# 01_USB_B_and_Power.net
KiCad netlist of a schematic drawn in Altium Designer
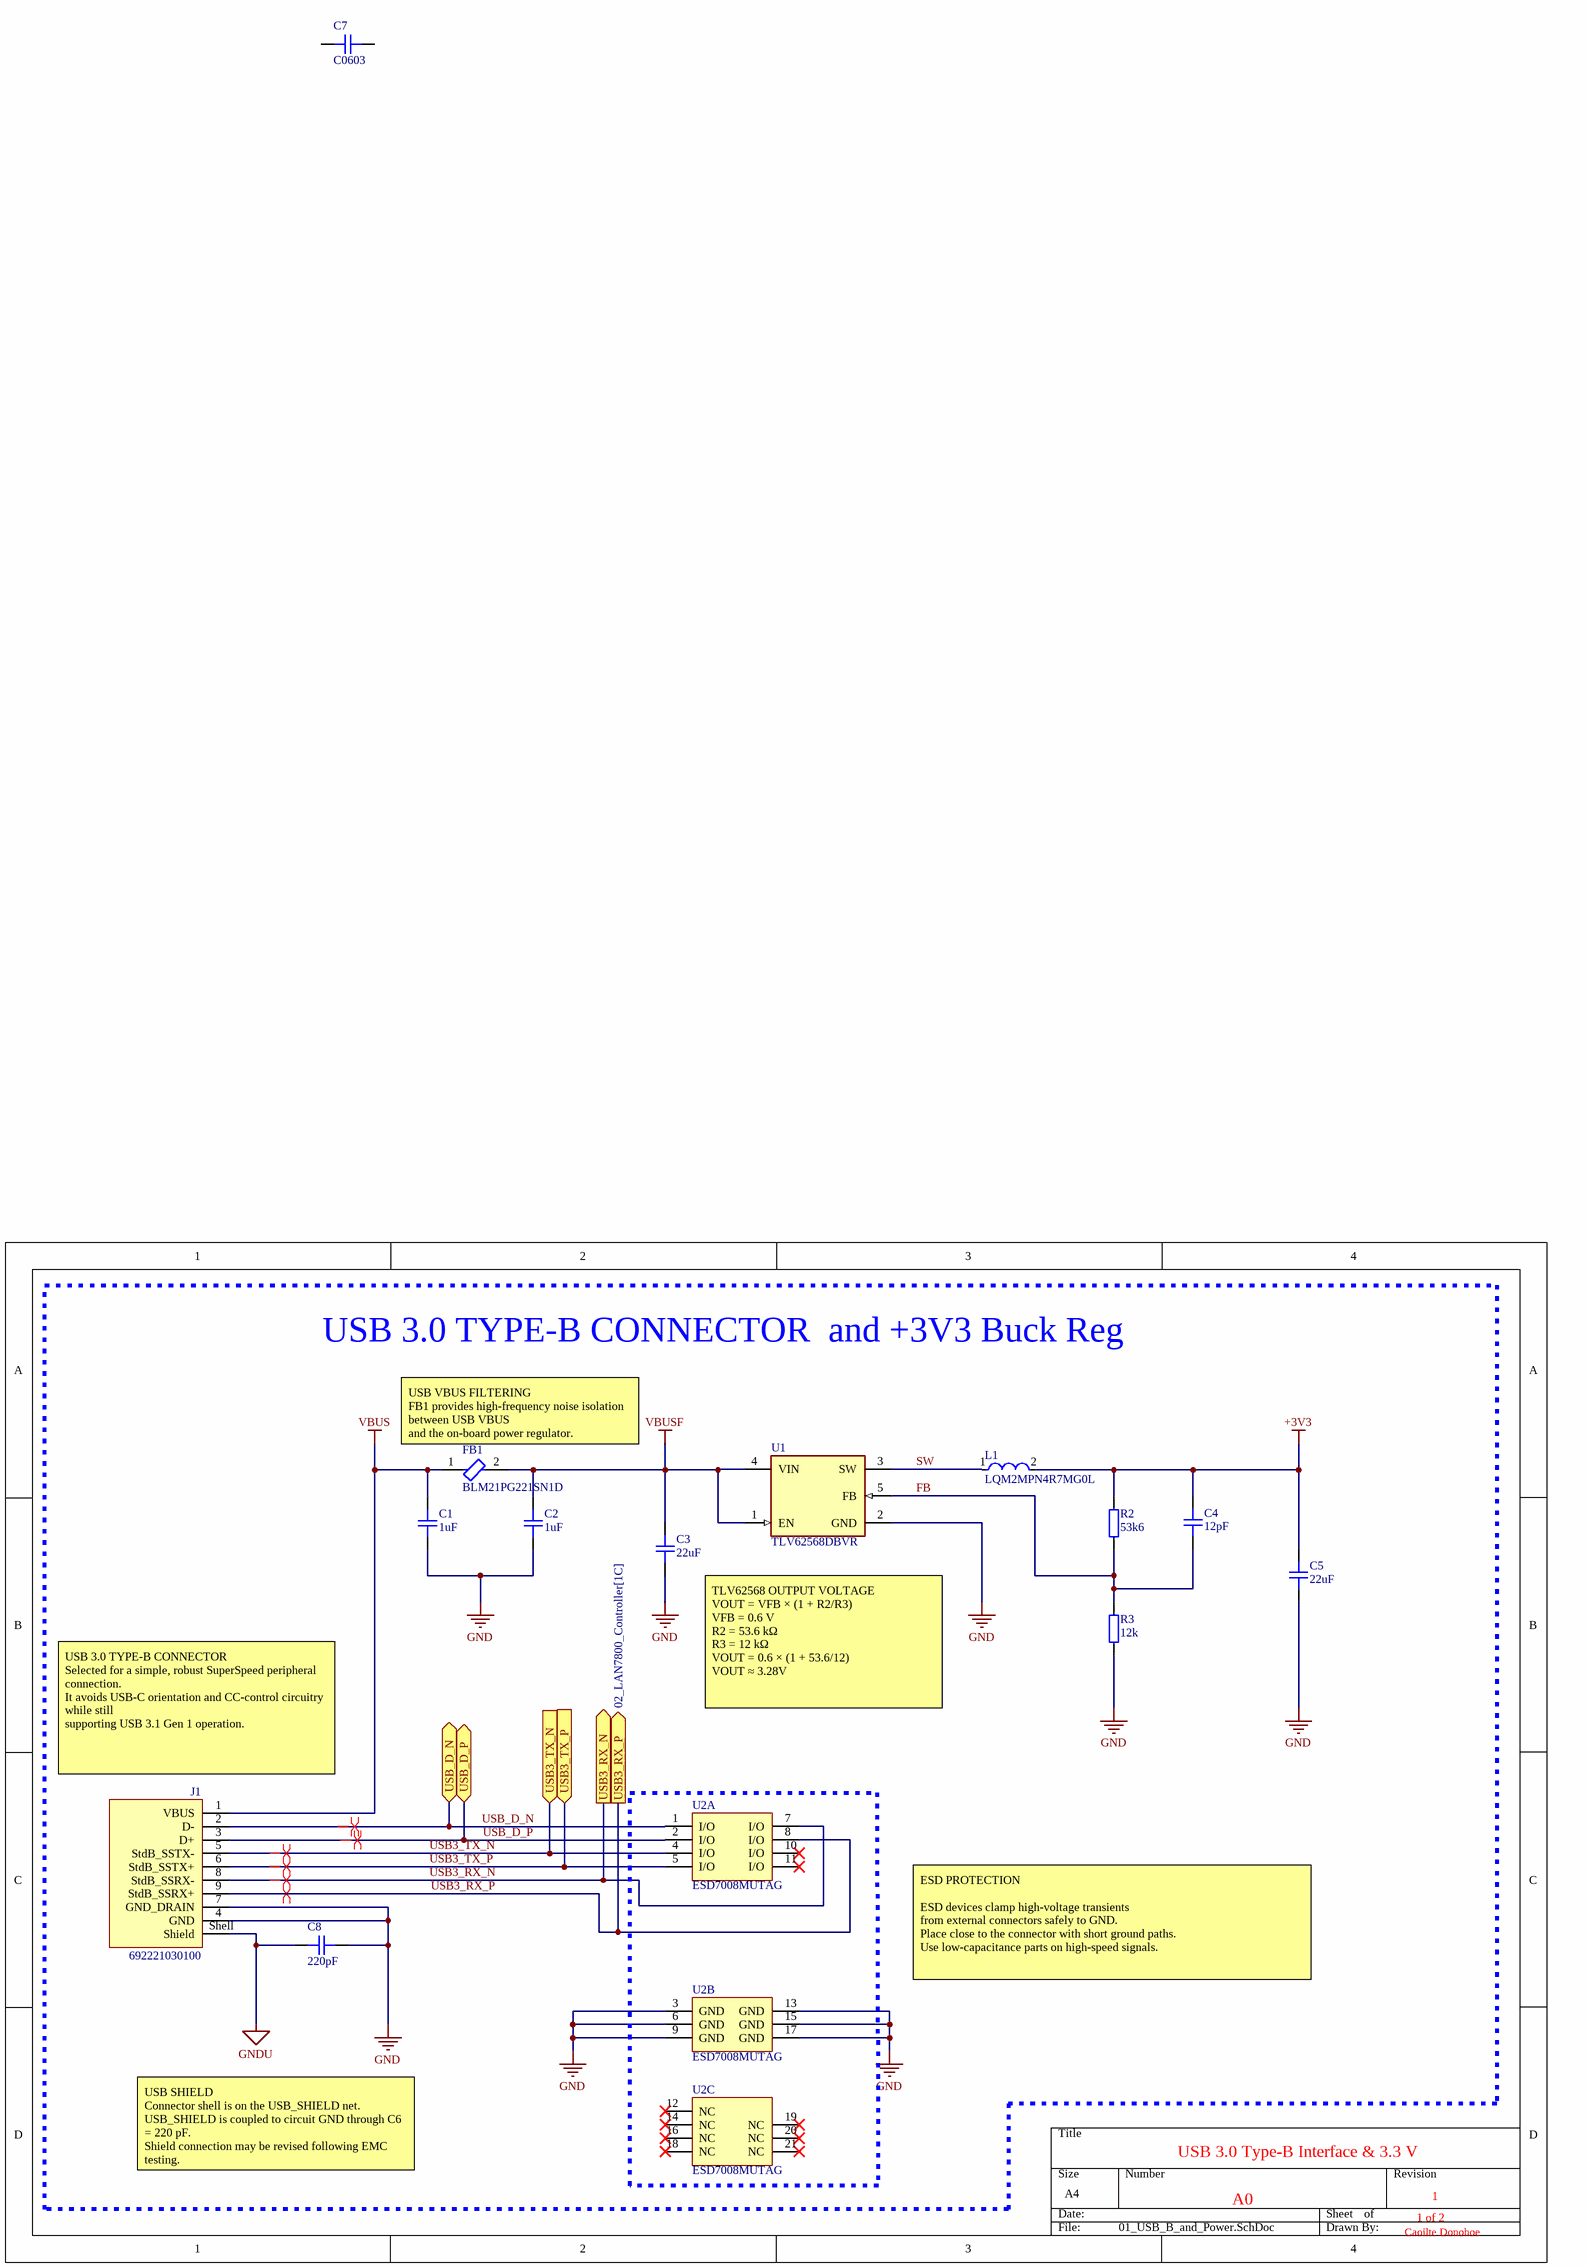
[diagram p0: 01_USB_B_and_Power.SchDoc]

(export (version "E")
  (design (tool "Eeschema 10.0.6"))
  (components
    (comp (ref "C1")
      (value "1uF")
      (footprint "CAP_0402")
      (description "Capacitor SMD 0402")
      (libsource (lib "Schematic-Lib-PMS_Caoilte") (part "CAP_0402"))
    )
    (comp (ref "C2")
      (value "1uF")
      (footprint "CAP_0402")
      (description "Capacitor SMD 0402")
      (libsource (lib "Schematic-Lib-PMS_Caoilte") (part "CAP_0402"))
    )
    (comp (ref "C3")
      (value "22uF")
      (footprint "CAP_0805")
      (description "Capacitor SMD 0805")
      (libsource (lib "Schematic-Lib-PMS_Caoilte") (part "CAP_0805"))
    )
    (comp (ref "C4")
      (value "12pF")
      (footprint "CAP_0402")
      (description "Capacitor SMD 0402")
      (libsource (lib "Schematic-Lib-PMS_Caoilte") (part "CAP_0402"))
    )
    (comp (ref "C5")
      (value "22uF")
      (footprint "CAP_0805")
      (description "Capacitor SMD 0805")
      (libsource (lib "Schematic-Lib-PMS_Caoilte") (part "CAP_0805"))
    )
    (comp (ref "C6")
      (value "22pF")
      (footprint "CAP_0603")
      (description "Capacitor SMD 0603")
      (libsource (lib "Schematic-Lib-PMS_Caoilte") (part "CAP_0603"))
    )
    (comp (ref "C7")
      (value "C0603")
      (footprint "CAP_0603")
      (description "Capacitor SMD 0603")
      (libsource (lib "Schematic-Lib-PMS_Caoilte") (part "CAP_0603"))
    )
    (comp (ref "C8")
      (value "220pF")
      (footprint "CAP_0603")
      (description "Capacitor SMD 0603")
      (libsource (lib "Schematic-Lib-PMS_Caoilte") (part "CAP_0603"))
    )
    (comp (ref "FB1")
      (value "BLM21PG221SN1D")
      (footprint "FP-BLM21-0_2-t0_85-e0_5-IPC_C")
      (description "Chip Ferrite Bead, 0805, 220Ω @ 100MHz, 0.045Ω, 25%, 2A")
      (fields (field (name "TOLERANCE") "25%"))
      (libsource (lib "LAN7800_USB_Ethernet_RevA") (part "CMP-0686-00610-3"))
    )
    (comp (ref "J1")
      (value "692221030100")
      (footprint "692221030100")
      (description "Conn USB 3.0 Type B RCP 9 POS (1.75mm/2.5)mm/1.25mm Solder RA Thru-Hole 9 Terminal 1 Port Tray")
      (libsource (lib "LAN7800_USB_Ethernet_RevA") (part "CMP-1502-03224-3"))
    )
    (comp (ref "L1")
      (value "LQM2MPN4R7MG0L")
      (footprint "FP-LQM2MPN_G0-IPC_B")
      (description "Multilayer Type Inductor for Power Lines, 0806 (2016), 4.7μH, 20%, 0.175Ω, 1.1A")
      (fields (field (name "TOLERANCE") "20%"))
      (libsource (lib "LAN7800_USB_Ethernet_RevA") (part "CMP-06042-016483-1"))
    )
    (comp (ref "R2")
      (value "53k6")
      (footprint "RES_0402")
      (description "Resistor SMD 0402")
      (libsource (lib "Schematic-Lib-PMS_Caoilte") (part "RES_0402"))
    )
    (comp (ref "R3")
      (value "12k")
      (footprint "RES_0402")
      (description "Resistor SMD 0402")
      (libsource (lib "Schematic-Lib-PMS_Caoilte") (part "RES_0402"))
    )
    (comp (ref "U1")
      (value "TLV62568DBVR")
      (footprint "FP-DBV0005A-MFG")
      (description "IC REG BUCK ADJ 1A SOT23-5")
      (fields
        (field (name "MANUFACTURER") "Texas Instruments")
        (field (name "OCTOPART") "https://octopart.com/tlv62568dbvr-texas+instruments-76926199")
      )
      (libsource (lib "LAN7800_USB_Ethernet_RevA") (part "CMP-04918-000009-1"))
    )
    (comp (ref "U2")
      (value "ESD7008MUTAG")
      (footprint "ONSC-UDFN-18-517BV_V")
      (fields (field (name "MANUFACTURER") "On Semiconductor"))
      (libsource (lib "LAN7800_USB_Ethernet_RevA") (part "CMP-1063-00247-1"))
    )
  )
  (nets
    (net (code "1") (name "+3V3") (class "Default")
      (node (ref "C4") (pin "2") (pinfunction "2_2") (pintype "passive"))
      (node (ref "C5") (pin "2") (pinfunction "2_2") (pintype "passive"))
      (node (ref "L1") (pin "2") (pinfunction "2_2") (pintype "passive"))
      (node (ref "R2") (pin "2") (pinfunction "2_2") (pintype "passive"))
    )
    (net (code "2") (name "/FB") (class "Default")
      (node (ref "C4") (pin "1") (pinfunction "1_1") (pintype "passive"))
      (node (ref "R2") (pin "1") (pinfunction "1_1") (pintype "passive"))
      (node (ref "R3") (pin "2") (pinfunction "2_2") (pintype "passive"))
      (node (ref "U1") (pin "5") (pinfunction "FB_5") (pintype "input"))
    )
    (net (code "3") (name "/SW") (class "Default")
      (node (ref "L1") (pin "1") (pinfunction "1_1") (pintype "passive"))
      (node (ref "U1") (pin "3") (pinfunction "SW_3") (pintype "passive"))
    )
    (net (code "4") (name "/USB3_RX_N") (class "Default")
      (node (ref "J1") (pin "8") (pinfunction "StdB_SSRX-_8") (pintype "passive"))
      (node (ref "U2") (pin "7") (pinfunction "I/O_7") (pintype "passive"))
    )
    (net (code "5") (name "/USB3_RX_P") (class "Default")
      (node (ref "J1") (pin "9") (pinfunction "StdB_SSRX+_9") (pintype "passive"))
      (node (ref "U2") (pin "8") (pinfunction "I/O_8") (pintype "passive"))
    )
    (net (code "6") (name "/USB3_TX_N") (class "Default")
      (node (ref "J1") (pin "5") (pinfunction "StdB_SSTX-_5") (pintype "passive"))
      (node (ref "U2") (pin "4") (pinfunction "I/O_4") (pintype "passive"))
    )
    (net (code "7") (name "/USB3_TX_P") (class "Default")
      (node (ref "J1") (pin "6") (pinfunction "StdB_SSTX+_6") (pintype "passive"))
      (node (ref "U2") (pin "5") (pinfunction "I/O_5") (pintype "passive"))
    )
    (net (code "8") (name "/USB_D_N") (class "Default")
      (node (ref "J1") (pin "2") (pinfunction "D-_2") (pintype "passive"))
      (node (ref "U2") (pin "1") (pinfunction "I/O_1") (pintype "passive"))
    )
    (net (code "9") (name "/USB_D_P") (class "Default")
      (node (ref "J1") (pin "3") (pinfunction "D+_3") (pintype "passive"))
      (node (ref "U2") (pin "2") (pinfunction "I/O_2") (pintype "passive"))
    )
    (net (code "10") (name "GND") (class "Default")
      (node (ref "C1") (pin "1") (pinfunction "1_1") (pintype "passive"))
      (node (ref "C2") (pin "1") (pinfunction "1_1") (pintype "passive"))
      (node (ref "C3") (pin "1") (pinfunction "1_1") (pintype "passive"))
      (node (ref "C5") (pin "1") (pinfunction "1_1") (pintype "passive"))
      (node (ref "C8") (pin "2") (pinfunction "2_2") (pintype "passive"))
      (node (ref "J1") (pin "4") (pinfunction "GND_4") (pintype "passive"))
      (node (ref "J1") (pin "7") (pinfunction "GND_DRAIN_7") (pintype "passive"))
      (node (ref "R3") (pin "1") (pinfunction "1_1") (pintype "passive"))
      (node (ref "U1") (pin "2") (pinfunction "GND_2") (pintype "power_in"))
      (node (ref "U2") (pin "13") (pinfunction "GND_13") (pintype "power_in"))
      (node (ref "U2") (pin "15") (pinfunction "GND_15") (pintype "power_in"))
      (node (ref "U2") (pin "17") (pinfunction "GND_17") (pintype "power_in"))
      (node (ref "U2") (pin "3") (pinfunction "GND_3") (pintype "power_in"))
      (node (ref "U2") (pin "6") (pinfunction "GND_6") (pintype "power_in"))
      (node (ref "U2") (pin "9") (pinfunction "GND_9") (pintype "power_in"))
    )
    (net (code "11") (name "GNDU") (class "Default")
      (node (ref "C8") (pin "1") (pinfunction "1_1") (pintype "passive"))
      (node (ref "J1") (pin "Shell") (pinfunction "Shield_Shell") (pintype "passive"))
    )
    (net (code "12") (name "VBUS") (class "Default")
      (node (ref "C1") (pin "2") (pinfunction "2_2") (pintype "passive"))
      (node (ref "FB1") (pin "1") (pinfunction "1_1") (pintype "passive"))
      (node (ref "J1") (pin "1") (pinfunction "VBUS_1") (pintype "passive"))
    )
    (net (code "13") (name "VBUSF") (class "Default")
      (node (ref "C2") (pin "2") (pinfunction "2_2") (pintype "passive"))
      (node (ref "C3") (pin "2") (pinfunction "2_2") (pintype "passive"))
      (node (ref "FB1") (pin "2") (pinfunction "2_2") (pintype "passive"))
      (node (ref "U1") (pin "1") (pinfunction "EN_1") (pintype "input"))
      (node (ref "U1") (pin "4") (pinfunction "VIN_4") (pintype "power_in"))
    )
    (net (code "14") (name "unconnected-(C6-Pad1)") (class "Default")
      (node (ref "C6") (pin "1") (pinfunction "1_1") (pintype "passive"))
    )
    (net (code "15") (name "unconnected-(C6-Pad2)") (class "Default")
      (node (ref "C6") (pin "2") (pinfunction "2_2") (pintype "passive"))
    )
    (net (code "16") (name "unconnected-(C7-Pad1)") (class "Default")
      (node (ref "C7") (pin "1") (pinfunction "1_1") (pintype "passive"))
    )
    (net (code "17") (name "unconnected-(C7-Pad2)") (class "Default")
      (node (ref "C7") (pin "2") (pinfunction "2_2") (pintype "passive"))
    )
    (net (code "18") (name "unconnected-(U2A-I{slash}O-Pad10)") (class "Default")
      (node (ref "U2") (pin "10") (pinfunction "I/O_10") (pintype "passive+no_connect"))
    )
    (net (code "19") (name "unconnected-(U2A-I{slash}O-Pad11)") (class "Default")
      (node (ref "U2") (pin "11") (pinfunction "I/O_11") (pintype "passive+no_connect"))
    )
    (net (code "20") (name "unconnected-(U2C-NC-Pad12)") (class "Default")
      (node (ref "U2") (pin "12") (pinfunction "NC_12") (pintype "passive+no_connect"))
    )
    (net (code "21") (name "unconnected-(U2C-NC-Pad14)") (class "Default")
      (node (ref "U2") (pin "14") (pinfunction "NC_14") (pintype "passive+no_connect"))
    )
    (net (code "22") (name "unconnected-(U2C-NC-Pad16)") (class "Default")
      (node (ref "U2") (pin "16") (pinfunction "NC_16") (pintype "passive+no_connect"))
    )
    (net (code "23") (name "unconnected-(U2C-NC-Pad18)") (class "Default")
      (node (ref "U2") (pin "18") (pinfunction "NC_18") (pintype "passive+no_connect"))
    )
    (net (code "24") (name "unconnected-(U2C-NC-Pad19)") (class "Default")
      (node (ref "U2") (pin "19") (pinfunction "NC_19") (pintype "passive+no_connect"))
    )
    (net (code "25") (name "unconnected-(U2C-NC-Pad20)") (class "Default")
      (node (ref "U2") (pin "20") (pinfunction "NC_20") (pintype "passive+no_connect"))
    )
    (net (code "26") (name "unconnected-(U2C-NC-Pad21)") (class "Default")
      (node (ref "U2") (pin "21") (pinfunction "NC_21") (pintype "passive+no_connect"))
    )
  )
)
